# RS485.net
KiCad netlist of a schematic drawn in Altium Designer
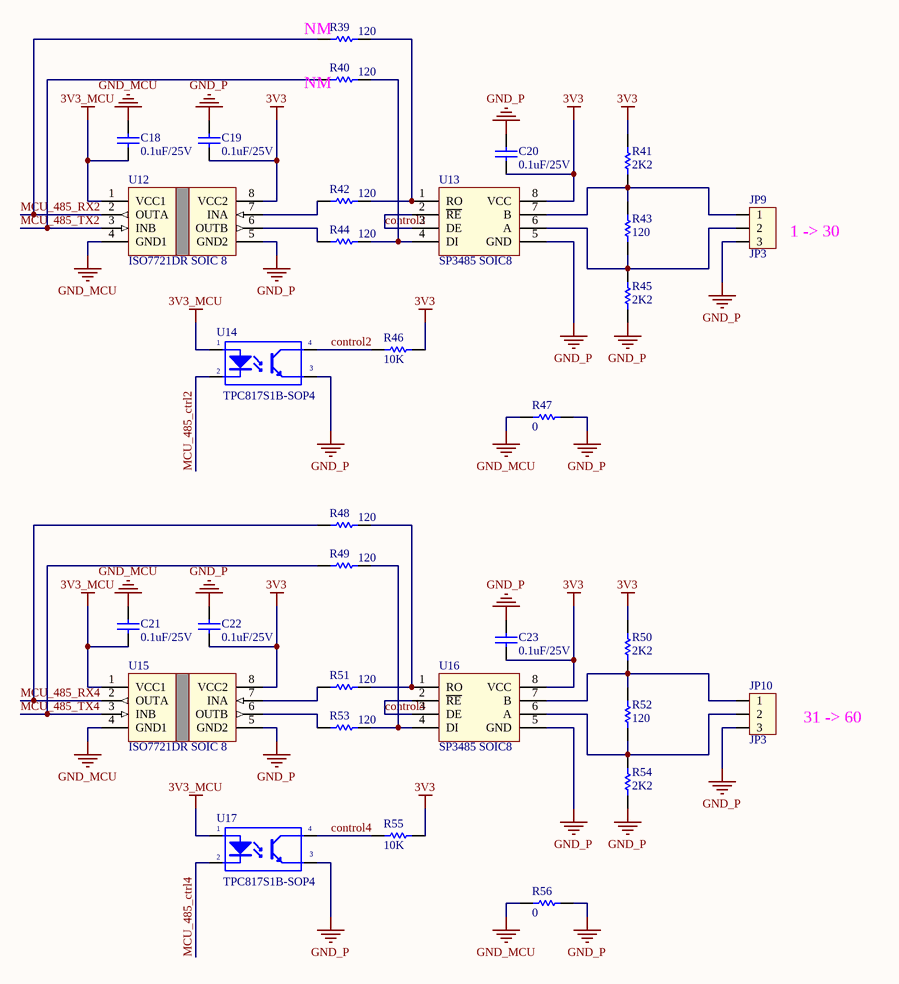
[diagram p0: RS485.SchDoc]

(export (version "E")
  (design (tool "Eeschema 10.0.6"))
  (components
    (comp (ref "C18")
      (value "0.1uF/25V")
      (footprint "Cap Ceramic 0805 SMD")
      (description "CAP CER 0.1UF 25V 10% X7R 0603")
      (fields
        (field (name "MANUFACTURER") "Murata Electronics North America")
        (field (name "MANUFACTURER PART NUMBER") "GRM188R71E104KA01D")
      )
      (libsource (lib "GSHT_181013") (part "0.1uF/25V/C0603/10%"))
    )
    (comp (ref "C19")
      (value "0.1uF/25V")
      (footprint "Cap Ceramic 0805 SMD")
      (description "CAP CER 0.1UF 25V 10% X7R 0603")
      (fields
        (field (name "MANUFACTURER") "Murata Electronics North America")
        (field (name "MANUFACTURER PART NUMBER") "GRM188R71E104KA01D")
      )
      (libsource (lib "GSHT_181013") (part "0.1uF/25V/C0603/10%"))
    )
    (comp (ref "C20")
      (value "0.1uF/25V")
      (footprint "Cap Ceramic 0805 SMD")
      (description "CAP CER 0.1UF 25V 10% X7R 0603")
      (fields
        (field (name "MANUFACTURER") "Murata Electronics North America")
        (field (name "MANUFACTURER PART NUMBER") "GRM188R71E104KA01D")
      )
      (libsource (lib "GSHT_181013") (part "0.1uF/25V/C0603/10%"))
    )
    (comp (ref "C21")
      (value "0.1uF/25V")
      (footprint "Cap Ceramic 0805 SMD")
      (description "CAP CER 0.1UF 25V 10% X7R 0603")
      (fields
        (field (name "MANUFACTURER") "Murata Electronics North America")
        (field (name "MANUFACTURER PART NUMBER") "GRM188R71E104KA01D")
      )
      (libsource (lib "GSHT_181013") (part "0.1uF/25V/C0603/10%"))
    )
    (comp (ref "C22")
      (value "0.1uF/25V")
      (footprint "Cap Ceramic 0805 SMD")
      (description "CAP CER 0.1UF 25V 10% X7R 0603")
      (fields
        (field (name "MANUFACTURER") "Murata Electronics North America")
        (field (name "MANUFACTURER PART NUMBER") "GRM188R71E104KA01D")
      )
      (libsource (lib "GSHT_181013") (part "0.1uF/25V/C0603/10%"))
    )
    (comp (ref "C23")
      (value "0.1uF/25V")
      (footprint "Cap Ceramic 0805 SMD")
      (description "CAP CER 0.1UF 25V 10% X7R 0603")
      (fields
        (field (name "MANUFACTURER") "Murata Electronics North America")
        (field (name "MANUFACTURER PART NUMBER") "GRM188R71E104KA01D")
      )
      (libsource (lib "GSHT_181013") (part "0.1uF/25V/C0603/10%"))
    )
    (comp (ref "JP9")
      (value "JP3")
      (footprint "2EDGR-5.08-03P")
      (description "Connector 3")
      (libsource (lib "lpson") (part "Con3"))
    )
    (comp (ref "JP10")
      (value "JP3")
      (footprint "2EDGR-5.08-03P")
      (description "Connector 3")
      (libsource (lib "lpson") (part "Con3"))
    )
    (comp (ref "R39")
      (value "120")
      (footprint "Res 0805 SMD")
      (description "RES SMD 249K OHM 1% 1/10W 0805")
      (fields
        (field (name "MANUFACTURER") "Yageo")
        (field (name "MANUFACTURER PART NUMBER") "RC0603FR-07249KL")
      )
      (libsource (lib "GSHT_181013") (part "249K/R0805/1%"))
    )
    (comp (ref "R40")
      (value "120")
      (footprint "Res 0805 SMD")
      (description "RES SMD 249K OHM 1% 1/10W 0805")
      (fields
        (field (name "MANUFACTURER") "Yageo")
        (field (name "MANUFACTURER PART NUMBER") "RC0603FR-07249KL")
      )
      (libsource (lib "GSHT_181013") (part "249K/R0805/1%"))
    )
    (comp (ref "R41")
      (value "2K2")
      (footprint "Res 0805 SMD")
      (description "RES SMD 249K OHM 1% 1/10W 0805")
      (fields
        (field (name "MANUFACTURER") "Yageo")
        (field (name "MANUFACTURER PART NUMBER") "RC0603FR-07249KL")
      )
      (libsource (lib "GSHT_181013") (part "249K/R0805/1%"))
    )
    (comp (ref "R42")
      (value "120")
      (footprint "Res 0805 SMD")
      (description "RES SMD 249K OHM 1% 1/10W 0805")
      (fields
        (field (name "MANUFACTURER") "Yageo")
        (field (name "MANUFACTURER PART NUMBER") "RC0603FR-07249KL")
      )
      (libsource (lib "GSHT_181013") (part "249K/R0805/1%"))
    )
    (comp (ref "R43")
      (value "120")
      (footprint "Res 0805 SMD")
      (description "RES SMD 249K OHM 1% 1/10W 0805")
      (fields
        (field (name "MANUFACTURER") "Yageo")
        (field (name "MANUFACTURER PART NUMBER") "RC0603FR-07249KL")
      )
      (libsource (lib "GSHT_181013") (part "249K/R0805/1%"))
    )
    (comp (ref "R44")
      (value "120")
      (footprint "Res 0805 SMD")
      (description "RES SMD 249K OHM 1% 1/10W 0805")
      (fields
        (field (name "MANUFACTURER") "Yageo")
        (field (name "MANUFACTURER PART NUMBER") "RC0603FR-07249KL")
      )
      (libsource (lib "GSHT_181013") (part "249K/R0805/1%"))
    )
    (comp (ref "R45")
      (value "2K2")
      (footprint "Res 0805 SMD")
      (description "RES SMD 249K OHM 1% 1/10W 0805")
      (fields
        (field (name "MANUFACTURER") "Yageo")
        (field (name "MANUFACTURER PART NUMBER") "RC0603FR-07249KL")
      )
      (libsource (lib "GSHT_181013") (part "249K/R0805/1%"))
    )
    (comp (ref "R46")
      (value "10K")
      (footprint "Res 0805 SMD")
      (description "RES SMD 249K OHM 1% 1/10W 0805")
      (fields
        (field (name "MANUFACTURER") "Yageo")
        (field (name "MANUFACTURER PART NUMBER") "RC0603FR-07249KL")
      )
      (libsource (lib "GSHT_181013") (part "249K/R0805/1%"))
    )
    (comp (ref "R47")
      (value "0")
      (footprint "Res 0805 SMD")
      (description "RES SMD 249K OHM 1% 1/10W 0805")
      (fields
        (field (name "MANUFACTURER") "Yageo")
        (field (name "MANUFACTURER PART NUMBER") "RC0603FR-07249KL")
      )
      (libsource (lib "GSHT_181013") (part "249K/R0805/1%"))
    )
    (comp (ref "R48")
      (value "120")
      (footprint "Res 0805 SMD")
      (description "RES SMD 249K OHM 1% 1/10W 0805")
      (fields
        (field (name "MANUFACTURER") "Yageo")
        (field (name "MANUFACTURER PART NUMBER") "RC0603FR-07249KL")
      )
      (libsource (lib "GSHT_181013") (part "249K/R0805/1%"))
    )
    (comp (ref "R49")
      (value "120")
      (footprint "Res 0805 SMD")
      (description "RES SMD 249K OHM 1% 1/10W 0805")
      (fields
        (field (name "MANUFACTURER") "Yageo")
        (field (name "MANUFACTURER PART NUMBER") "RC0603FR-07249KL")
      )
      (libsource (lib "GSHT_181013") (part "249K/R0805/1%"))
    )
    (comp (ref "R50")
      (value "2K2")
      (footprint "Res 0805 SMD")
      (description "RES SMD 249K OHM 1% 1/10W 0805")
      (fields
        (field (name "MANUFACTURER") "Yageo")
        (field (name "MANUFACTURER PART NUMBER") "RC0603FR-07249KL")
      )
      (libsource (lib "GSHT_181013") (part "249K/R0805/1%"))
    )
    (comp (ref "R51")
      (value "120")
      (footprint "Res 0805 SMD")
      (description "RES SMD 249K OHM 1% 1/10W 0805")
      (fields
        (field (name "MANUFACTURER") "Yageo")
        (field (name "MANUFACTURER PART NUMBER") "RC0603FR-07249KL")
      )
      (libsource (lib "GSHT_181013") (part "249K/R0805/1%"))
    )
    (comp (ref "R52")
      (value "120")
      (footprint "Res 0805 SMD")
      (description "RES SMD 249K OHM 1% 1/10W 0805")
      (fields
        (field (name "MANUFACTURER") "Yageo")
        (field (name "MANUFACTURER PART NUMBER") "RC0603FR-07249KL")
      )
      (libsource (lib "GSHT_181013") (part "249K/R0805/1%"))
    )
    (comp (ref "R53")
      (value "120")
      (footprint "Res 0805 SMD")
      (description "RES SMD 249K OHM 1% 1/10W 0805")
      (fields
        (field (name "MANUFACTURER") "Yageo")
        (field (name "MANUFACTURER PART NUMBER") "RC0603FR-07249KL")
      )
      (libsource (lib "GSHT_181013") (part "249K/R0805/1%"))
    )
    (comp (ref "R54")
      (value "2K2")
      (footprint "Res 0805 SMD")
      (description "RES SMD 249K OHM 1% 1/10W 0805")
      (fields
        (field (name "MANUFACTURER") "Yageo")
        (field (name "MANUFACTURER PART NUMBER") "RC0603FR-07249KL")
      )
      (libsource (lib "GSHT_181013") (part "249K/R0805/1%"))
    )
    (comp (ref "R55")
      (value "10K")
      (footprint "Res 0805 SMD")
      (description "RES SMD 249K OHM 1% 1/10W 0805")
      (fields
        (field (name "MANUFACTURER") "Yageo")
        (field (name "MANUFACTURER PART NUMBER") "RC0603FR-07249KL")
      )
      (libsource (lib "GSHT_181013") (part "249K/R0805/1%"))
    )
    (comp (ref "R56")
      (value "0")
      (footprint "Res 0805 SMD")
      (description "RES SMD 249K OHM 1% 1/10W 0805")
      (fields
        (field (name "MANUFACTURER") "Yageo")
        (field (name "MANUFACTURER PART NUMBER") "RC0603FR-07249KL")
      )
      (libsource (lib "GSHT_181013") (part "249K/R0805/1%"))
    )
    (comp (ref "U12")
      (value "ISO7721DR SOIC 8")
      (footprint "ISO7721D SOIC-8 10.9mm")
      (description "ISO772x High-Speed, Robust EMC, Reinforced Dual-Channel Digital Isolators")
      (libsource (lib "lpson") (part "ISO7721DR SOIC 8"))
    )
    (comp (ref "U13")
      (value "SP3485 SOIC8")
      (footprint "SP3485 SOIC-8 3.9mm")
      (libsource (lib "lpson") (part "SP3485 SOIC8"))
    )
    (comp (ref "U14")
      (value "TPC817S1B-SOP4")
      (footprint "TPC817-4SOP")
      (description "Optoisolator Transistor Output 5000Vrms 1 Channel 4-SOP")
      (libsource (lib "lpson") (part "PC817"))
    )
    (comp (ref "U15")
      (value "ISO7721DR SOIC 8")
      (footprint "ISO7721D SOIC-8 10.9mm")
      (description "ISO772x High-Speed, Robust EMC, Reinforced Dual-Channel Digital Isolators")
      (libsource (lib "lpson") (part "ISO7721DR SOIC 8"))
    )
    (comp (ref "U16")
      (value "SP3485 SOIC8")
      (footprint "SP3485 SOIC-8 3.9mm")
      (libsource (lib "lpson") (part "SP3485 SOIC8"))
    )
    (comp (ref "U17")
      (value "TPC817S1B-SOP4")
      (footprint "TPC817-4SOP")
      (description "Optoisolator Transistor Output 5000Vrms 1 Channel 4-SOP")
      (libsource (lib "lpson") (part "PC817"))
    )
  )
  (nets
    (net (code "1") (name "/MCU_485_RX2") (class "Default")
      (node (ref "R39") (pin "1") (pinfunction "1_1") (pintype "passive"))
      (node (ref "U12") (pin "2") (pinfunction "OUTA_2") (pintype "output"))
    )
    (net (code "2") (name "/MCU_485_RX4") (class "Default")
      (node (ref "R48") (pin "1") (pinfunction "1_1") (pintype "passive"))
      (node (ref "U15") (pin "2") (pinfunction "OUTA_2") (pintype "output"))
    )
    (net (code "3") (name "/MCU_485_TX2") (class "Default")
      (node (ref "R40") (pin "1") (pinfunction "1_1") (pintype "passive"))
      (node (ref "U12") (pin "3") (pinfunction "INB_3") (pintype "input"))
    )
    (net (code "4") (name "/MCU_485_TX4") (class "Default")
      (node (ref "R49") (pin "1") (pinfunction "1_1") (pintype "passive"))
      (node (ref "U15") (pin "3") (pinfunction "INB_3") (pintype "input"))
    )
    (net (code "5") (name "/MCU_485_ctrl2") (class "Default")
      (node (ref "U14") (pin "2") (pinfunction "K_2") (pintype "passive"))
    )
    (net (code "6") (name "/MCU_485_ctrl4") (class "Default")
      (node (ref "U17") (pin "2") (pinfunction "K_2") (pintype "passive"))
    )
    (net (code "7") (name "/control2") (class "Default")
      (node (ref "R46") (pin "2") (pinfunction "2_2") (pintype "passive"))
      (node (ref "U13") (pin "2") (pinfunction "~{RE}_2") (pintype "passive"))
      (node (ref "U13") (pin "3") (pinfunction "DE_3") (pintype "passive"))
      (node (ref "U14") (pin "4") (pinfunction "C_4") (pintype "passive"))
    )
    (net (code "8") (name "/control4") (class "Default")
      (node (ref "R55") (pin "2") (pinfunction "2_2") (pintype "passive"))
      (node (ref "U16") (pin "2") (pinfunction "~{RE}_2") (pintype "passive"))
      (node (ref "U16") (pin "3") (pinfunction "DE_3") (pintype "passive"))
      (node (ref "U17") (pin "4") (pinfunction "C_4") (pintype "passive"))
    )
    (net (code "9") (name "3V3") (class "Default")
      (node (ref "C19") (pin "1") (pinfunction "1_1") (pintype "passive"))
      (node (ref "C20") (pin "1") (pinfunction "1_1") (pintype "passive"))
      (node (ref "C22") (pin "1") (pinfunction "1_1") (pintype "passive"))
      (node (ref "C23") (pin "1") (pinfunction "1_1") (pintype "passive"))
      (node (ref "R41") (pin "2") (pinfunction "2_2") (pintype "passive"))
      (node (ref "R46") (pin "1") (pinfunction "1_1") (pintype "passive"))
      (node (ref "R50") (pin "2") (pinfunction "2_2") (pintype "passive"))
      (node (ref "R55") (pin "1") (pinfunction "1_1") (pintype "passive"))
      (node (ref "U12") (pin "8") (pinfunction "VCC2_8") (pintype "passive"))
      (node (ref "U13") (pin "8") (pinfunction "VCC_8") (pintype "passive"))
      (node (ref "U15") (pin "8") (pinfunction "VCC2_8") (pintype "passive"))
      (node (ref "U16") (pin "8") (pinfunction "VCC_8") (pintype "passive"))
    )
    (net (code "10") (name "3V3_MCU") (class "Default")
      (node (ref "C18") (pin "1") (pinfunction "1_1") (pintype "passive"))
      (node (ref "C21") (pin "1") (pinfunction "1_1") (pintype "passive"))
      (node (ref "U12") (pin "1") (pinfunction "VCC1_1") (pintype "passive"))
      (node (ref "U14") (pin "1") (pinfunction "A_1") (pintype "passive"))
      (node (ref "U15") (pin "1") (pinfunction "VCC1_1") (pintype "passive"))
      (node (ref "U17") (pin "1") (pinfunction "A_1") (pintype "passive"))
    )
    (net (code "11") (name "GND_MCU") (class "Default")
      (node (ref "C18") (pin "2") (pinfunction "2_2") (pintype "passive"))
      (node (ref "C21") (pin "2") (pinfunction "2_2") (pintype "passive"))
      (node (ref "R47") (pin "2") (pinfunction "2_2") (pintype "passive"))
      (node (ref "R56") (pin "2") (pinfunction "2_2") (pintype "passive"))
      (node (ref "U12") (pin "4") (pinfunction "GND1_4") (pintype "passive"))
      (node (ref "U15") (pin "4") (pinfunction "GND1_4") (pintype "passive"))
    )
    (net (code "12") (name "GND_P") (class "Default")
      (node (ref "C19") (pin "2") (pinfunction "2_2") (pintype "passive"))
      (node (ref "C20") (pin "2") (pinfunction "2_2") (pintype "passive"))
      (node (ref "C22") (pin "2") (pinfunction "2_2") (pintype "passive"))
      (node (ref "C23") (pin "2") (pinfunction "2_2") (pintype "passive"))
      (node (ref "JP10") (pin "3") (pinfunction "3_3") (pintype "passive"))
      (node (ref "JP9") (pin "3") (pinfunction "3_3") (pintype "passive"))
      (node (ref "R45") (pin "1") (pinfunction "1_1") (pintype "passive"))
      (node (ref "R47") (pin "1") (pinfunction "1_1") (pintype "passive"))
      (node (ref "R54") (pin "1") (pinfunction "1_1") (pintype "passive"))
      (node (ref "R56") (pin "1") (pinfunction "1_1") (pintype "passive"))
      (node (ref "U12") (pin "5") (pinfunction "GND2_5") (pintype "passive"))
      (node (ref "U13") (pin "5") (pinfunction "GND_5") (pintype "passive"))
      (node (ref "U14") (pin "3") (pinfunction "E_3") (pintype "passive"))
      (node (ref "U15") (pin "5") (pinfunction "GND2_5") (pintype "passive"))
      (node (ref "U16") (pin "5") (pinfunction "GND_5") (pintype "passive"))
      (node (ref "U17") (pin "3") (pinfunction "E_3") (pintype "passive"))
    )
    (net (code "13") (name "Net-(U12-INA)") (class "Default")
      (node (ref "R42") (pin "1") (pinfunction "1_1") (pintype "passive"))
      (node (ref "U12") (pin "7") (pinfunction "INA_7") (pintype "input"))
    )
    (net (code "14") (name "Net-(U12-OUTB)") (class "Default")
      (node (ref "R44") (pin "1") (pinfunction "1_1") (pintype "passive"))
      (node (ref "U12") (pin "6") (pinfunction "OUTB_6") (pintype "output"))
    )
    (net (code "15") (name "Net-(U13-A)") (class "Default")
      (node (ref "JP9") (pin "2") (pinfunction "2_2") (pintype "passive"))
      (node (ref "R43") (pin "1") (pinfunction "1_1") (pintype "passive"))
      (node (ref "R45") (pin "2") (pinfunction "2_2") (pintype "passive"))
      (node (ref "U13") (pin "6") (pinfunction "A_6") (pintype "passive"))
    )
    (net (code "16") (name "Net-(U13-B)") (class "Default")
      (node (ref "JP9") (pin "1") (pinfunction "1_1") (pintype "passive"))
      (node (ref "R41") (pin "1") (pinfunction "1_1") (pintype "passive"))
      (node (ref "R43") (pin "2") (pinfunction "2_2") (pintype "passive"))
      (node (ref "U13") (pin "7") (pinfunction "B_7") (pintype "passive"))
    )
    (net (code "17") (name "Net-(U13-DI)") (class "Default")
      (node (ref "R40") (pin "2") (pinfunction "2_2") (pintype "passive"))
      (node (ref "R44") (pin "2") (pinfunction "2_2") (pintype "passive"))
      (node (ref "U13") (pin "4") (pinfunction "DI_4") (pintype "passive"))
    )
    (net (code "18") (name "Net-(U13-RO)") (class "Default")
      (node (ref "R39") (pin "2") (pinfunction "2_2") (pintype "passive"))
      (node (ref "R42") (pin "2") (pinfunction "2_2") (pintype "passive"))
      (node (ref "U13") (pin "1") (pinfunction "RO_1") (pintype "passive"))
    )
    (net (code "19") (name "Net-(U15-INA)") (class "Default")
      (node (ref "R51") (pin "1") (pinfunction "1_1") (pintype "passive"))
      (node (ref "U15") (pin "7") (pinfunction "INA_7") (pintype "input"))
    )
    (net (code "20") (name "Net-(U15-OUTB)") (class "Default")
      (node (ref "R53") (pin "1") (pinfunction "1_1") (pintype "passive"))
      (node (ref "U15") (pin "6") (pinfunction "OUTB_6") (pintype "output"))
    )
    (net (code "21") (name "Net-(U16-A)") (class "Default")
      (node (ref "JP10") (pin "2") (pinfunction "2_2") (pintype "passive"))
      (node (ref "R52") (pin "1") (pinfunction "1_1") (pintype "passive"))
      (node (ref "R54") (pin "2") (pinfunction "2_2") (pintype "passive"))
      (node (ref "U16") (pin "6") (pinfunction "A_6") (pintype "passive"))
    )
    (net (code "22") (name "Net-(U16-B)") (class "Default")
      (node (ref "JP10") (pin "1") (pinfunction "1_1") (pintype "passive"))
      (node (ref "R50") (pin "1") (pinfunction "1_1") (pintype "passive"))
      (node (ref "R52") (pin "2") (pinfunction "2_2") (pintype "passive"))
      (node (ref "U16") (pin "7") (pinfunction "B_7") (pintype "passive"))
    )
    (net (code "23") (name "Net-(U16-DI)") (class "Default")
      (node (ref "R49") (pin "2") (pinfunction "2_2") (pintype "passive"))
      (node (ref "R53") (pin "2") (pinfunction "2_2") (pintype "passive"))
      (node (ref "U16") (pin "4") (pinfunction "DI_4") (pintype "passive"))
    )
    (net (code "24") (name "Net-(U16-RO)") (class "Default")
      (node (ref "R48") (pin "2") (pinfunction "2_2") (pintype "passive"))
      (node (ref "R51") (pin "2") (pinfunction "2_2") (pintype "passive"))
      (node (ref "U16") (pin "1") (pinfunction "RO_1") (pintype "passive"))
    )
  )
)
